# 464342_21-005_3_2.net
KiCad netlist of a schematic drawn in Altium Designer
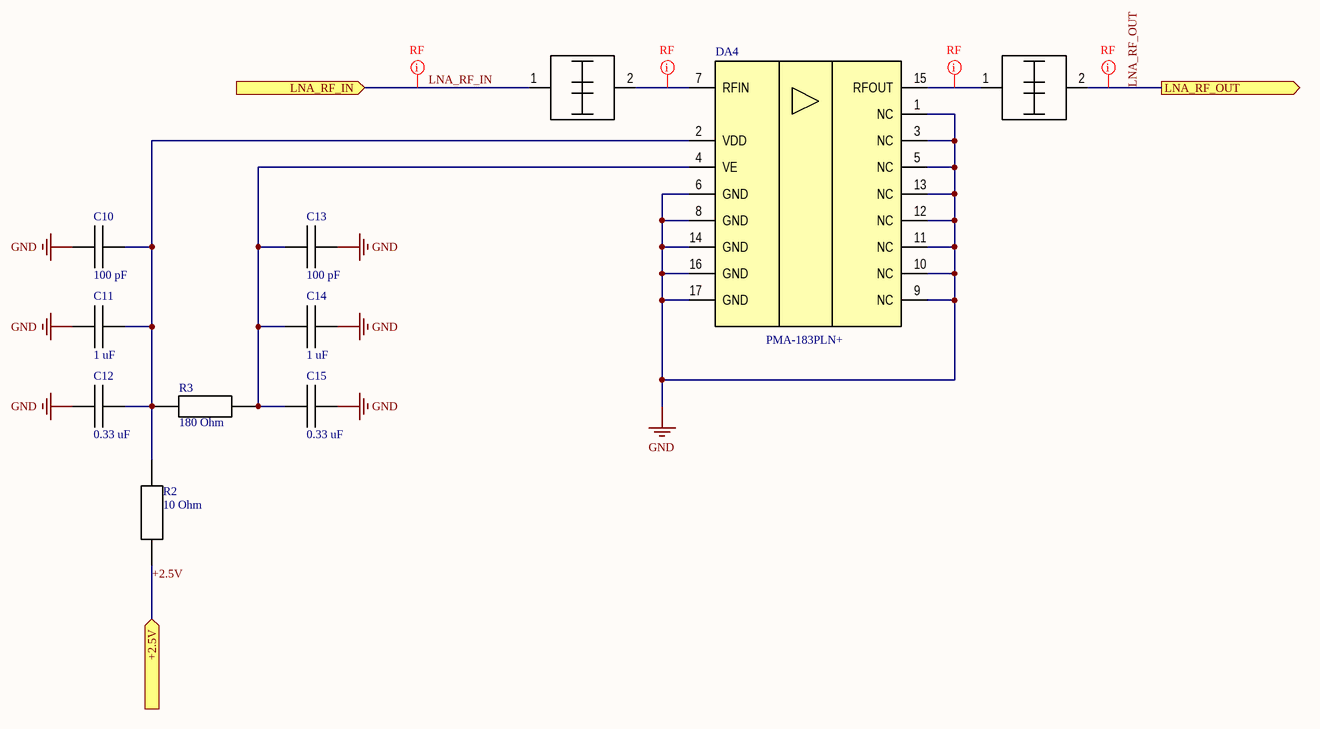
[diagram p0: МПСУ.464342.21-005Э3 Лист2.SchDoc]

(export (version "E")
  (design (tool "Eeschema 10.0.6"))
  (components
    (comp (ref "C10")
      (value "100 pF")
      (footprint "CAPC100X50X55L20N")
      (description "Capacitor, generic")
      (fields (field (name "TOLERANCE") "± %10"))
      (libsource (lib "Discrete") (part "Capacitor"))
    )
    (comp (ref "C11")
      (value "1 uF")
      (footprint "CAPC160X80X90L30N")
      (description "Capacitor, generic")
      (fields (field (name "PARTNUMBER") "X5R") (field (name "TOLERANCE") "± %10"))
      (libsource (lib "Discrete") (part "Capacitor"))
    )
    (comp (ref "C12")
      (value "0.33 uF")
      (footprint "CAPC200X125X95L50N")
      (description "Capacitor, generic")
      (fields (field (name "TOLERANCE") "± %10"))
      (libsource (lib "Discrete") (part "Capacitor"))
    )
    (comp (ref "C13")
      (value "100 pF")
      (footprint "CAPC100X50X55L20N")
      (description "Capacitor, generic")
      (fields (field (name "TOLERANCE") "± %10"))
      (libsource (lib "Discrete") (part "Capacitor"))
    )
    (comp (ref "C14")
      (value "1 uF")
      (footprint "CAPC160X80X90L30N")
      (description "Capacitor, generic")
      (fields (field (name "PARTNUMBER") "X5R") (field (name "TOLERANCE") "± %10"))
      (libsource (lib "Discrete") (part "Capacitor"))
    )
    (comp (ref "C15")
      (value "0.33 uF")
      (footprint "CAPC200X125X95L50N")
      (description "Capacitor, generic")
      (fields (field (name "TOLERANCE") "± %10"))
      (libsource (lib "Discrete") (part "Capacitor"))
    )
    (comp (ref "DA4")
      (value "PMA-183PLN+")
      (footprint "JV2579")
      (description "SMT Low Noise Amplifier, 6000 - 18000 MHz, 50Ω")
      (fields (field (name "MANUFACTURER") "Mini-Circuits"))
      (libsource (lib "Amplifiers") (part "PMA-183PLN+"))
    )
    (comp (ref "R2")
      (value "10 Ohm")
      (footprint "RESC100X50X40L25N")
      (description "Resistor, generic")
      (fields (field (name "TOLERANCE") "± 5%") (field (name "POWER") "63 mW"))
      (libsource (lib "Discrete") (part "Resistor"))
    )
    (comp (ref "R3")
      (value "180 Ohm")
      (footprint "RESC100X50X40L25N")
      (description "Resistor, generic")
      (fields (field (name "TOLERANCE") "± 5%") (field (name "POWER") "63 mW"))
      (libsource (lib "") (part "Resistor_1"))
    )
    (comp (ref "W4")
      (value "Matching")
      (footprint "MATCHING_LNA_IN")
      (description "Matching MTEE")
      (libsource (lib "Microstrip") (part "Matching_1"))
    )
    (comp (ref "W5")
      (value "Matching")
      (footprint "MATCHING_LNA_OUT")
      (description "Matching MTEE")
      (libsource (lib "Microstrip") (part "Matching_1"))
    )
  )
  (nets
    (net (code "1") (name "/+2.5V") (class "Default")
      (node (ref "R2") (pin "1") (pinfunction "1_1") (pintype "passive"))
    )
    (net (code "2") (name "/LNA_RF_IN") (class "Default")
      (node (ref "W4") (pin "1") (pinfunction "1_1") (pintype "passive"))
    )
    (net (code "3") (name "/LNA_RF_OUT") (class "Default")
      (node (ref "W5") (pin "2") (pinfunction "2_2") (pintype "passive"))
    )
    (net (code "4") (name "GND") (class "Default")
      (node (ref "C10") (pin "1") (pinfunction "1_1") (pintype "passive"))
      (node (ref "C11") (pin "1") (pinfunction "1_1") (pintype "passive"))
      (node (ref "C12") (pin "1") (pinfunction "1_1") (pintype "passive"))
      (node (ref "C13") (pin "2") (pinfunction "2_2") (pintype "passive"))
      (node (ref "C14") (pin "2") (pinfunction "2_2") (pintype "passive"))
      (node (ref "C15") (pin "2") (pinfunction "2_2") (pintype "passive"))
      (node (ref "DA4") (pin "1") (pinfunction "NC_1") (pintype "passive"))
      (node (ref "DA4") (pin "10") (pinfunction "NC_10") (pintype "passive"))
      (node (ref "DA4") (pin "11") (pinfunction "NC_11") (pintype "passive"))
      (node (ref "DA4") (pin "12") (pinfunction "NC_12") (pintype "passive"))
      (node (ref "DA4") (pin "13") (pinfunction "NC_13") (pintype "passive"))
      (node (ref "DA4") (pin "14") (pinfunction "GND_14") (pintype "passive"))
      (node (ref "DA4") (pin "16") (pinfunction "GND_16") (pintype "passive"))
      (node (ref "DA4") (pin "17") (pinfunction "GND_17") (pintype "passive"))
      (node (ref "DA4") (pin "3") (pinfunction "NC_3") (pintype "passive"))
      (node (ref "DA4") (pin "5") (pinfunction "NC_5") (pintype "passive"))
      (node (ref "DA4") (pin "6") (pinfunction "GND_6") (pintype "passive"))
      (node (ref "DA4") (pin "8") (pinfunction "GND_8") (pintype "passive"))
      (node (ref "DA4") (pin "9") (pinfunction "NC_9") (pintype "passive"))
    )
    (net (code "5") (name "Net-(DA4-RFIN)") (class "Default")
      (node (ref "DA4") (pin "7") (pinfunction "RFIN_7") (pintype "passive"))
      (node (ref "W4") (pin "2") (pinfunction "2_2") (pintype "passive"))
    )
    (net (code "6") (name "Net-(DA4-RFOUT)") (class "Default")
      (node (ref "DA4") (pin "15") (pinfunction "RFOUT_15") (pintype "passive"))
      (node (ref "W5") (pin "1") (pinfunction "1_1") (pintype "passive"))
    )
    (net (code "7") (name "Net-(DA4-VDD)") (class "Default")
      (node (ref "C10") (pin "2") (pinfunction "2_2") (pintype "passive"))
      (node (ref "C11") (pin "2") (pinfunction "2_2") (pintype "passive"))
      (node (ref "C12") (pin "2") (pinfunction "2_2") (pintype "passive"))
      (node (ref "DA4") (pin "2") (pinfunction "VDD_2") (pintype "passive"))
      (node (ref "R2") (pin "2") (pinfunction "2_2") (pintype "passive"))
      (node (ref "R3") (pin "1") (pinfunction "1_1") (pintype "passive"))
    )
    (net (code "8") (name "Net-(DA4-VE)") (class "Default")
      (node (ref "C13") (pin "1") (pinfunction "1_1") (pintype "passive"))
      (node (ref "C14") (pin "1") (pinfunction "1_1") (pintype "passive"))
      (node (ref "C15") (pin "1") (pinfunction "1_1") (pintype "passive"))
      (node (ref "DA4") (pin "4") (pinfunction "VE_4") (pintype "passive"))
      (node (ref "R3") (pin "2") (pinfunction "2_2") (pintype "passive"))
    )
  )
)
